# ShiftRegV1_3.net
KiCad netlist of a schematic drawn in EasyEDA
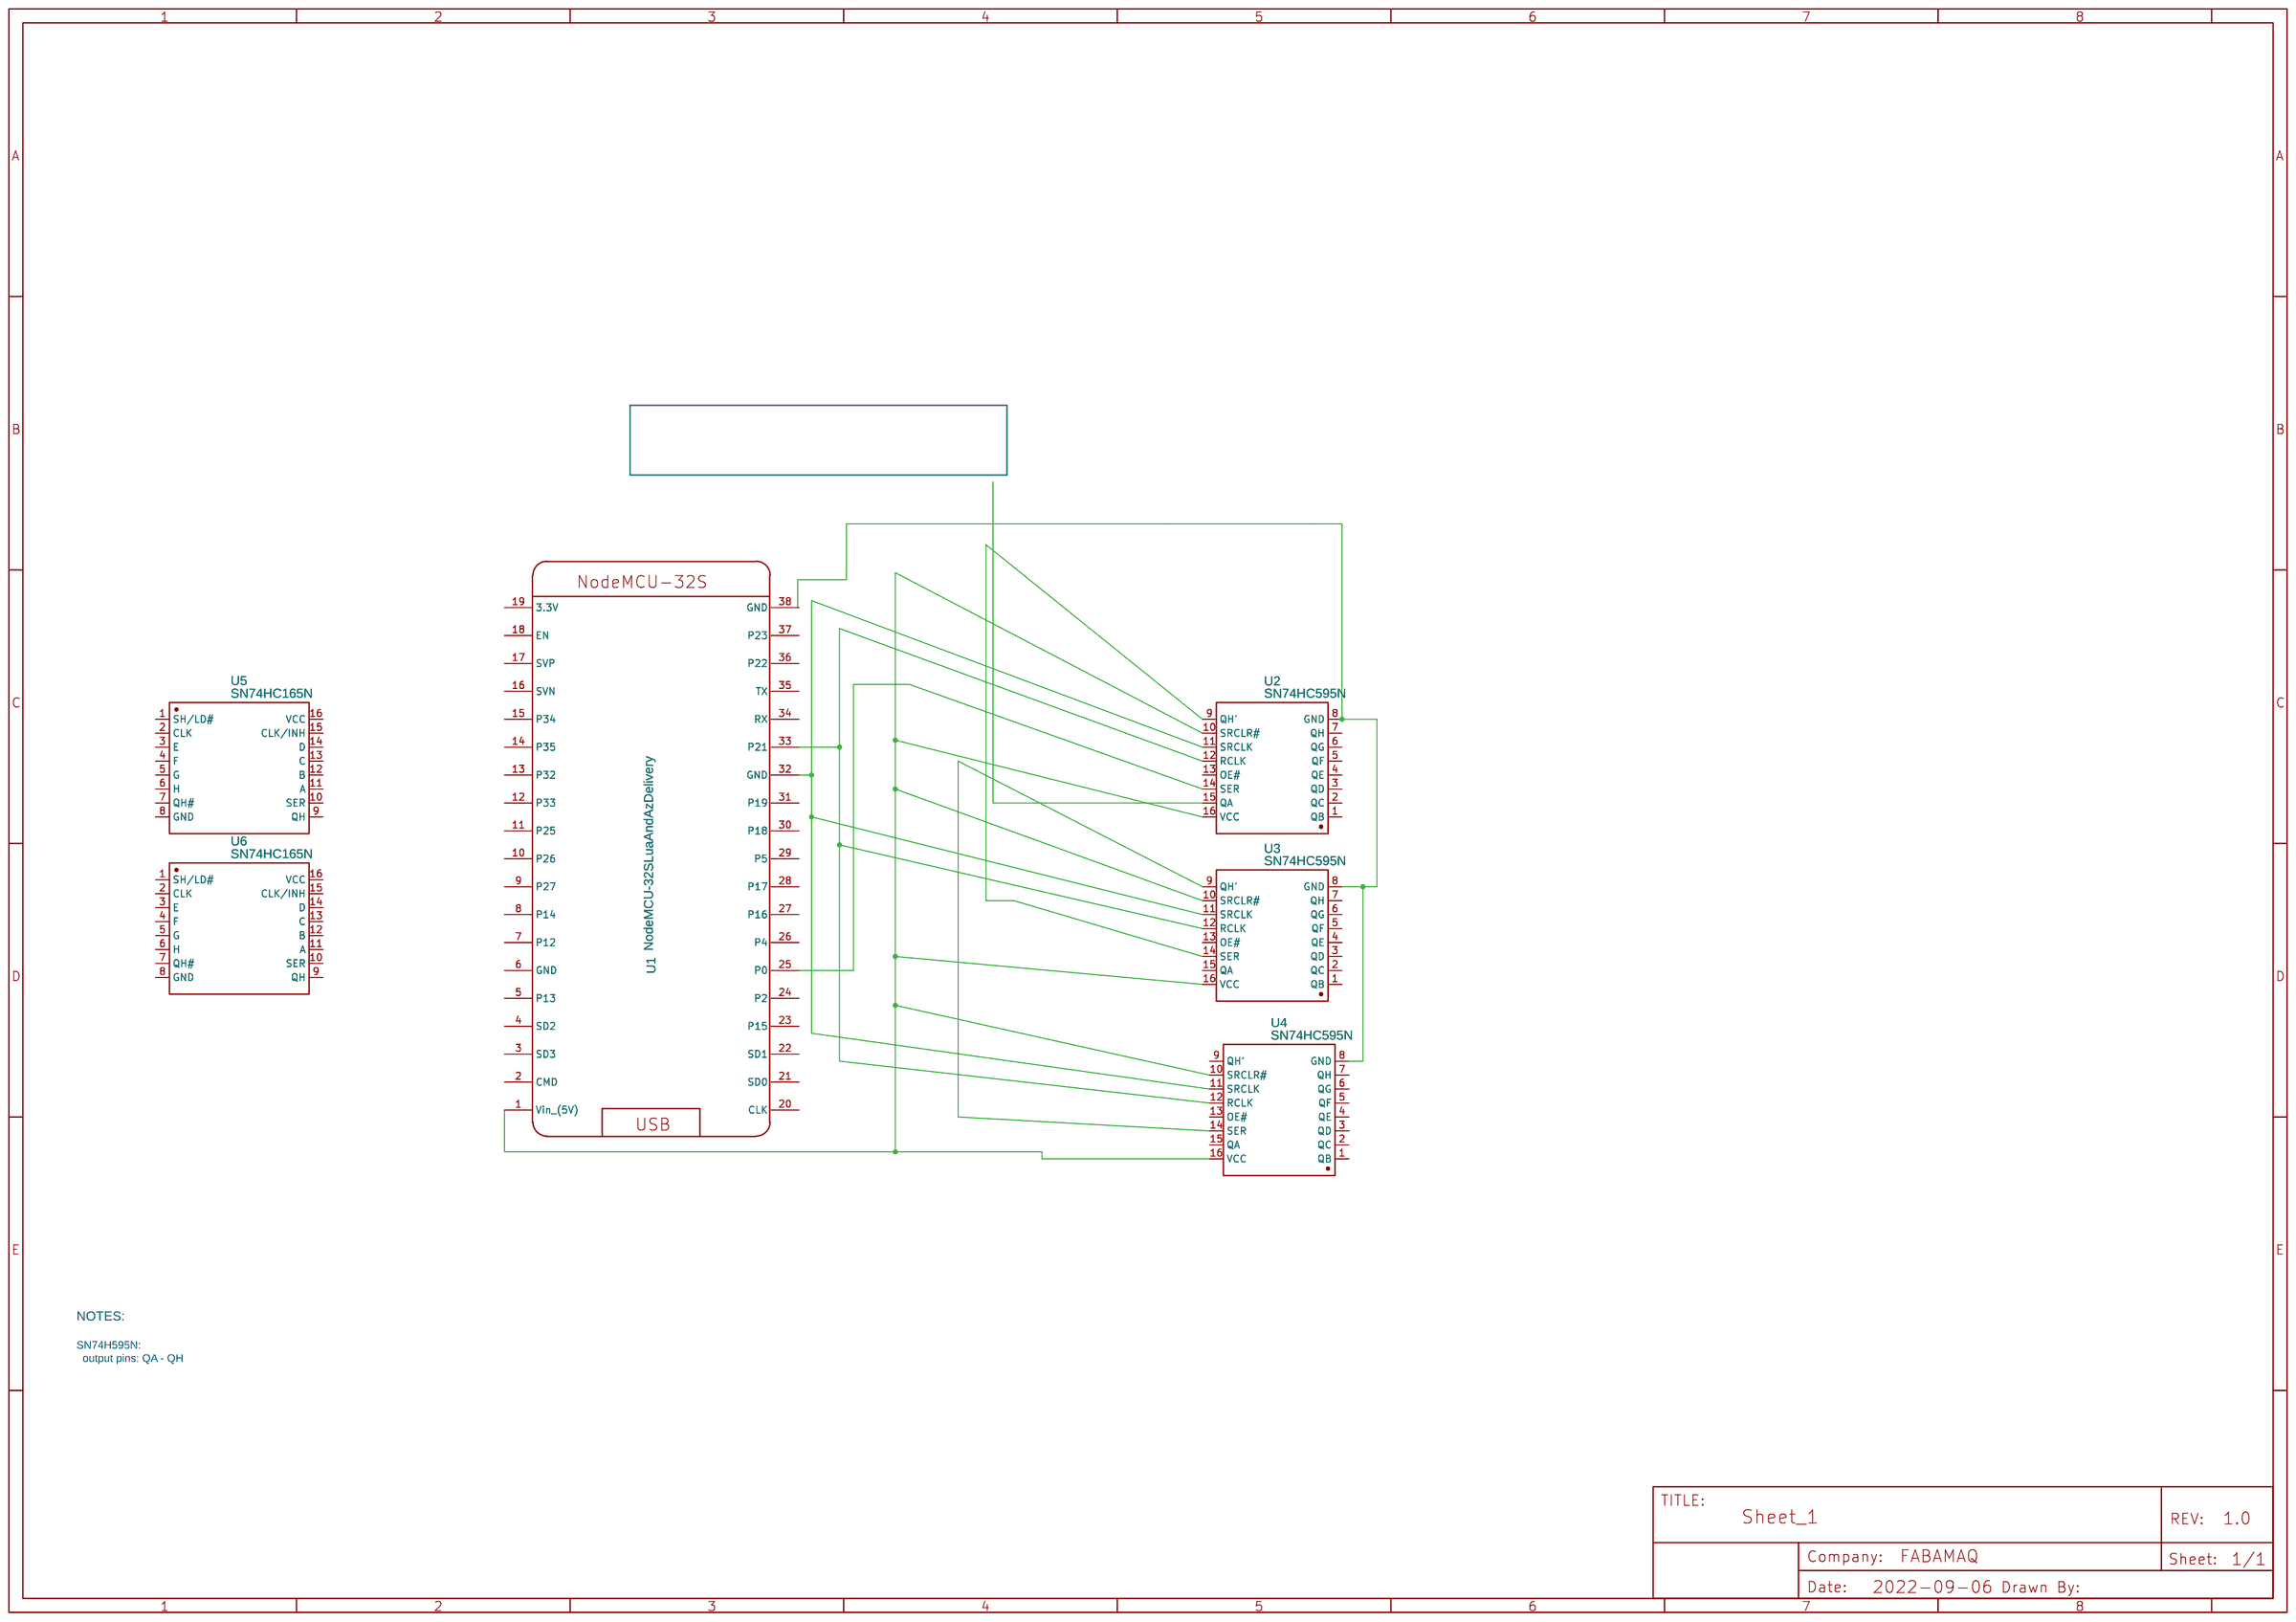
[diagram p0: schematic sheet]

(export (version "E")
  (design (tool "Eeschema 10.0.6"))
  (components
    (comp (ref "U1")
      (value "NodeMCU-32SLuaAndAzDelivery")
      (fields
        (field (name "BOM_Manufacturer Part") "NodeMCU-32SLua")
        (field (name "BOM_Supplier Part") "C111436")
      )
      (libsource (lib "") (part "NodeMCU-32SLuaAndAzDelivery"))
    )
    (comp (ref "U2")
      (value "SN74HC595N")
      (fields (field (name "BOM_Supplier Part") "C78711"))
      (libsource (lib "") (part "SN74HC595N"))
    )
    (comp (ref "U3")
      (value "SN74HC595N")
      (fields (field (name "BOM_Supplier Part") "C78711"))
      (libsource (lib "") (part "SN74HC595N"))
    )
    (comp (ref "U4")
      (value "SN74HC595N")
      (fields (field (name "BOM_Supplier Part") "C78711"))
      (libsource (lib "") (part "SN74HC595N"))
    )
    (comp (ref "U5")
      (value "SN74HC165N")
      (fields (field (name "BOM_Supplier Part") "C2909"))
      (libsource (lib "") (part "SN74HC165N"))
    )
    (comp (ref "U6")
      (value "SN74HC165N")
      (fields (field (name "BOM_Supplier Part") "C2909"))
      (libsource (lib "") (part "SN74HC165N"))
    )
  )
  (nets
    (net (code "1") (name "Net-(U1-P0)") (class "Default")
      (node (ref "U1") (pin "25") (pinfunction "P0_25") (pintype "unspecified"))
      (node (ref "U2") (pin "14") (pinfunction "SER_14") (pintype "unspecified"))
    )
    (net (code "2") (name "Net-(U1-P21)") (class "Default")
      (node (ref "U1") (pin "33") (pinfunction "P21_33") (pintype "unspecified"))
      (node (ref "U2") (pin "12") (pinfunction "RCLK_12") (pintype "unspecified"))
      (node (ref "U3") (pin "12") (pinfunction "RCLK_12") (pintype "unspecified"))
      (node (ref "U4") (pin "12") (pinfunction "RCLK_12") (pintype "unspecified"))
    )
    (net (code "3") (name "Net-(U1-Vin_(5V))") (class "Default")
      (node (ref "U1") (pin "1") (pinfunction "Vin_(5V)_1") (pintype "unspecified"))
      (node (ref "U2") (pin "10") (pinfunction "SRCLR#_10") (pintype "unspecified"))
      (node (ref "U2") (pin "16") (pinfunction "VCC_16") (pintype "unspecified"))
      (node (ref "U3") (pin "10") (pinfunction "SRCLR#_10") (pintype "unspecified"))
      (node (ref "U3") (pin "16") (pinfunction "VCC_16") (pintype "unspecified"))
      (node (ref "U4") (pin "10") (pinfunction "SRCLR#_10") (pintype "unspecified"))
      (node (ref "U4") (pin "16") (pinfunction "VCC_16") (pintype "unspecified"))
    )
    (net (code "4") (name "Net-(U2-GND)") (class "Default")
      (node (ref "U1") (pin "38") (pinfunction "GND_38") (pintype "unspecified"))
      (node (ref "U2") (pin "8") (pinfunction "GND_8") (pintype "unspecified"))
      (node (ref "U3") (pin "8") (pinfunction "GND_8") (pintype "unspecified"))
      (node (ref "U4") (pin "8") (pinfunction "GND_8") (pintype "unspecified"))
    )
    (net (code "5") (name "Net-(U2-QH')") (class "Default")
      (node (ref "U2") (pin "9") (pinfunction "QH'_9") (pintype "unspecified"))
      (node (ref "U3") (pin "14") (pinfunction "SER_14") (pintype "unspecified"))
    )
    (net (code "6") (name "Net-(U2-SRCLK)") (class "Default")
      (node (ref "U1") (pin "32") (pinfunction "GND_32") (pintype "unspecified"))
      (node (ref "U2") (pin "11") (pinfunction "SRCLK_11") (pintype "unspecified"))
      (node (ref "U3") (pin "11") (pinfunction "SRCLK_11") (pintype "unspecified"))
      (node (ref "U4") (pin "11") (pinfunction "SRCLK_11") (pintype "unspecified"))
    )
    (net (code "7") (name "Net-(U3-QH')") (class "Default")
      (node (ref "U3") (pin "9") (pinfunction "QH'_9") (pintype "unspecified"))
      (node (ref "U4") (pin "14") (pinfunction "SER_14") (pintype "unspecified"))
    )
    (net (code "8") (name "unconnected-(U1-3.3V-Pad19)") (class "Default")
      (node (ref "U1") (pin "19") (pinfunction "3.3V_19") (pintype "unspecified"))
    )
    (net (code "9") (name "unconnected-(U1-CLK-Pad20)") (class "Default")
      (node (ref "U1") (pin "20") (pinfunction "CLK_20") (pintype "unspecified"))
    )
    (net (code "10") (name "unconnected-(U1-CMD-Pad2)") (class "Default")
      (node (ref "U1") (pin "2") (pinfunction "CMD_2") (pintype "unspecified"))
    )
    (net (code "11") (name "unconnected-(U1-EN-Pad18)") (class "Default")
      (node (ref "U1") (pin "18") (pinfunction "EN_18") (pintype "unspecified"))
    )
    (net (code "12") (name "unconnected-(U1-GND-Pad6)") (class "Default")
      (node (ref "U1") (pin "6") (pinfunction "GND_6") (pintype "unspecified"))
    )
    (net (code "13") (name "unconnected-(U1-P2-Pad24)") (class "Default")
      (node (ref "U1") (pin "24") (pinfunction "P2_24") (pintype "unspecified"))
    )
    (net (code "14") (name "unconnected-(U1-P4-Pad26)") (class "Default")
      (node (ref "U1") (pin "26") (pinfunction "P4_26") (pintype "unspecified"))
    )
    (net (code "15") (name "unconnected-(U1-P5-Pad29)") (class "Default")
      (node (ref "U1") (pin "29") (pinfunction "P5_29") (pintype "unspecified"))
    )
    (net (code "16") (name "unconnected-(U1-P12-Pad7)") (class "Default")
      (node (ref "U1") (pin "7") (pinfunction "P12_7") (pintype "unspecified"))
    )
    (net (code "17") (name "unconnected-(U1-P13-Pad5)") (class "Default")
      (node (ref "U1") (pin "5") (pinfunction "P13_5") (pintype "unspecified"))
    )
    (net (code "18") (name "unconnected-(U1-P14-Pad8)") (class "Default")
      (node (ref "U1") (pin "8") (pinfunction "P14_8") (pintype "unspecified"))
    )
    (net (code "19") (name "unconnected-(U1-P15-Pad23)") (class "Default")
      (node (ref "U1") (pin "23") (pinfunction "P15_23") (pintype "unspecified"))
    )
    (net (code "20") (name "unconnected-(U1-P16-Pad27)") (class "Default")
      (node (ref "U1") (pin "27") (pinfunction "P16_27") (pintype "unspecified"))
    )
    (net (code "21") (name "unconnected-(U1-P17-Pad28)") (class "Default")
      (node (ref "U1") (pin "28") (pinfunction "P17_28") (pintype "unspecified"))
    )
    (net (code "22") (name "unconnected-(U1-P18-Pad30)") (class "Default")
      (node (ref "U1") (pin "30") (pinfunction "P18_30") (pintype "unspecified"))
    )
    (net (code "23") (name "unconnected-(U1-P19-Pad31)") (class "Default")
      (node (ref "U1") (pin "31") (pinfunction "P19_31") (pintype "unspecified"))
    )
    (net (code "24") (name "unconnected-(U1-P22-Pad36)") (class "Default")
      (node (ref "U1") (pin "36") (pinfunction "P22_36") (pintype "unspecified"))
    )
    (net (code "25") (name "unconnected-(U1-P23-Pad37)") (class "Default")
      (node (ref "U1") (pin "37") (pinfunction "P23_37") (pintype "unspecified"))
    )
    (net (code "26") (name "unconnected-(U1-P25-Pad11)") (class "Default")
      (node (ref "U1") (pin "11") (pinfunction "P25_11") (pintype "unspecified"))
    )
    (net (code "27") (name "unconnected-(U1-P26-Pad10)") (class "Default")
      (node (ref "U1") (pin "10") (pinfunction "P26_10") (pintype "unspecified"))
    )
    (net (code "28") (name "unconnected-(U1-P27-Pad9)") (class "Default")
      (node (ref "U1") (pin "9") (pinfunction "P27_9") (pintype "unspecified"))
    )
    (net (code "29") (name "unconnected-(U1-P32-Pad13)") (class "Default")
      (node (ref "U1") (pin "13") (pinfunction "P32_13") (pintype "unspecified"))
    )
    (net (code "30") (name "unconnected-(U1-P33-Pad12)") (class "Default")
      (node (ref "U1") (pin "12") (pinfunction "P33_12") (pintype "unspecified"))
    )
    (net (code "31") (name "unconnected-(U1-P34-Pad15)") (class "Default")
      (node (ref "U1") (pin "15") (pinfunction "P34_15") (pintype "unspecified"))
    )
    (net (code "32") (name "unconnected-(U1-P35-Pad14)") (class "Default")
      (node (ref "U1") (pin "14") (pinfunction "P35_14") (pintype "unspecified"))
    )
    (net (code "33") (name "unconnected-(U1-RX-Pad34)") (class "Default")
      (node (ref "U1") (pin "34") (pinfunction "RX_34") (pintype "unspecified"))
    )
    (net (code "34") (name "unconnected-(U1-SD0-Pad21)") (class "Default")
      (node (ref "U1") (pin "21") (pinfunction "SD0_21") (pintype "unspecified"))
    )
    (net (code "35") (name "unconnected-(U1-SD1-Pad22)") (class "Default")
      (node (ref "U1") (pin "22") (pinfunction "SD1_22") (pintype "unspecified"))
    )
    (net (code "36") (name "unconnected-(U1-SD2-Pad4)") (class "Default")
      (node (ref "U1") (pin "4") (pinfunction "SD2_4") (pintype "unspecified"))
    )
    (net (code "37") (name "unconnected-(U1-SD3-Pad3)") (class "Default")
      (node (ref "U1") (pin "3") (pinfunction "SD3_3") (pintype "unspecified"))
    )
    (net (code "38") (name "unconnected-(U1-SVN-Pad16)") (class "Default")
      (node (ref "U1") (pin "16") (pinfunction "SVN_16") (pintype "unspecified"))
    )
    (net (code "39") (name "unconnected-(U1-SVP-Pad17)") (class "Default")
      (node (ref "U1") (pin "17") (pinfunction "SVP_17") (pintype "unspecified"))
    )
    (net (code "40") (name "unconnected-(U1-TX-Pad35)") (class "Default")
      (node (ref "U1") (pin "35") (pinfunction "TX_35") (pintype "unspecified"))
    )
    (net (code "41") (name "unconnected-(U2-OE#-Pad13)") (class "Default")
      (node (ref "U2") (pin "13") (pinfunction "OE#_13") (pintype "unspecified"))
    )
    (net (code "42") (name "unconnected-(U2-QA-Pad15)") (class "Default")
      (node (ref "U2") (pin "15") (pinfunction "QA_15") (pintype "unspecified"))
    )
    (net (code "43") (name "unconnected-(U2-QB-Pad1)") (class "Default")
      (node (ref "U2") (pin "1") (pinfunction "QB_1") (pintype "unspecified"))
    )
    (net (code "44") (name "unconnected-(U2-QC-Pad2)") (class "Default")
      (node (ref "U2") (pin "2") (pinfunction "QC_2") (pintype "unspecified"))
    )
    (net (code "45") (name "unconnected-(U2-QD-Pad3)") (class "Default")
      (node (ref "U2") (pin "3") (pinfunction "QD_3") (pintype "unspecified"))
    )
    (net (code "46") (name "unconnected-(U2-QE-Pad4)") (class "Default")
      (node (ref "U2") (pin "4") (pinfunction "QE_4") (pintype "unspecified"))
    )
    (net (code "47") (name "unconnected-(U2-QF-Pad5)") (class "Default")
      (node (ref "U2") (pin "5") (pinfunction "QF_5") (pintype "unspecified"))
    )
    (net (code "48") (name "unconnected-(U2-QG-Pad6)") (class "Default")
      (node (ref "U2") (pin "6") (pinfunction "QG_6") (pintype "unspecified"))
    )
    (net (code "49") (name "unconnected-(U2-QH-Pad7)") (class "Default")
      (node (ref "U2") (pin "7") (pinfunction "QH_7") (pintype "unspecified"))
    )
    (net (code "50") (name "unconnected-(U3-OE#-Pad13)") (class "Default")
      (node (ref "U3") (pin "13") (pinfunction "OE#_13") (pintype "unspecified"))
    )
    (net (code "51") (name "unconnected-(U3-QA-Pad15)") (class "Default")
      (node (ref "U3") (pin "15") (pinfunction "QA_15") (pintype "unspecified"))
    )
    (net (code "52") (name "unconnected-(U3-QB-Pad1)") (class "Default")
      (node (ref "U3") (pin "1") (pinfunction "QB_1") (pintype "unspecified"))
    )
    (net (code "53") (name "unconnected-(U3-QC-Pad2)") (class "Default")
      (node (ref "U3") (pin "2") (pinfunction "QC_2") (pintype "unspecified"))
    )
    (net (code "54") (name "unconnected-(U3-QD-Pad3)") (class "Default")
      (node (ref "U3") (pin "3") (pinfunction "QD_3") (pintype "unspecified"))
    )
    (net (code "55") (name "unconnected-(U3-QE-Pad4)") (class "Default")
      (node (ref "U3") (pin "4") (pinfunction "QE_4") (pintype "unspecified"))
    )
    (net (code "56") (name "unconnected-(U3-QF-Pad5)") (class "Default")
      (node (ref "U3") (pin "5") (pinfunction "QF_5") (pintype "unspecified"))
    )
    (net (code "57") (name "unconnected-(U3-QG-Pad6)") (class "Default")
      (node (ref "U3") (pin "6") (pinfunction "QG_6") (pintype "unspecified"))
    )
    (net (code "58") (name "unconnected-(U3-QH-Pad7)") (class "Default")
      (node (ref "U3") (pin "7") (pinfunction "QH_7") (pintype "unspecified"))
    )
    (net (code "59") (name "unconnected-(U4-OE#-Pad13)") (class "Default")
      (node (ref "U4") (pin "13") (pinfunction "OE#_13") (pintype "unspecified"))
    )
    (net (code "60") (name "unconnected-(U4-QA-Pad15)") (class "Default")
      (node (ref "U4") (pin "15") (pinfunction "QA_15") (pintype "unspecified"))
    )
    (net (code "61") (name "unconnected-(U4-QB-Pad1)") (class "Default")
      (node (ref "U4") (pin "1") (pinfunction "QB_1") (pintype "unspecified"))
    )
    (net (code "62") (name "unconnected-(U4-QC-Pad2)") (class "Default")
      (node (ref "U4") (pin "2") (pinfunction "QC_2") (pintype "unspecified"))
    )
    (net (code "63") (name "unconnected-(U4-QD-Pad3)") (class "Default")
      (node (ref "U4") (pin "3") (pinfunction "QD_3") (pintype "unspecified"))
    )
    (net (code "64") (name "unconnected-(U4-QE-Pad4)") (class "Default")
      (node (ref "U4") (pin "4") (pinfunction "QE_4") (pintype "unspecified"))
    )
    (net (code "65") (name "unconnected-(U4-QF-Pad5)") (class "Default")
      (node (ref "U4") (pin "5") (pinfunction "QF_5") (pintype "unspecified"))
    )
    (net (code "66") (name "unconnected-(U4-QG-Pad6)") (class "Default")
      (node (ref "U4") (pin "6") (pinfunction "QG_6") (pintype "unspecified"))
    )
    (net (code "67") (name "unconnected-(U4-QH'-Pad9)") (class "Default")
      (node (ref "U4") (pin "9") (pinfunction "QH'_9") (pintype "unspecified"))
    )
    (net (code "68") (name "unconnected-(U4-QH-Pad7)") (class "Default")
      (node (ref "U4") (pin "7") (pinfunction "QH_7") (pintype "unspecified"))
    )
    (net (code "69") (name "unconnected-(U5-A-Pad11)") (class "Default")
      (node (ref "U5") (pin "11") (pinfunction "A_11") (pintype "unspecified"))
    )
    (net (code "70") (name "unconnected-(U5-B-Pad12)") (class "Default")
      (node (ref "U5") (pin "12") (pinfunction "B_12") (pintype "unspecified"))
    )
    (net (code "71") (name "unconnected-(U5-C-Pad13)") (class "Default")
      (node (ref "U5") (pin "13") (pinfunction "C_13") (pintype "unspecified"))
    )
    (net (code "72") (name "unconnected-(U5-CLK-Pad2)") (class "Default")
      (node (ref "U5") (pin "2") (pinfunction "CLK_2") (pintype "unspecified"))
    )
    (net (code "73") (name "unconnected-(U5-CLK{slash}INH-Pad15)") (class "Default")
      (node (ref "U5") (pin "15") (pinfunction "CLK/INH_15") (pintype "unspecified"))
    )
    (net (code "74") (name "unconnected-(U5-D-Pad14)") (class "Default")
      (node (ref "U5") (pin "14") (pinfunction "D_14") (pintype "unspecified"))
    )
    (net (code "75") (name "unconnected-(U5-E-Pad3)") (class "Default")
      (node (ref "U5") (pin "3") (pinfunction "E_3") (pintype "unspecified"))
    )
    (net (code "76") (name "unconnected-(U5-F-Pad4)") (class "Default")
      (node (ref "U5") (pin "4") (pinfunction "F_4") (pintype "unspecified"))
    )
    (net (code "77") (name "unconnected-(U5-G-Pad5)") (class "Default")
      (node (ref "U5") (pin "5") (pinfunction "G_5") (pintype "unspecified"))
    )
    (net (code "78") (name "unconnected-(U5-GND-Pad8)") (class "Default")
      (node (ref "U5") (pin "8") (pinfunction "GND_8") (pintype "unspecified"))
    )
    (net (code "79") (name "unconnected-(U5-H-Pad6)") (class "Default")
      (node (ref "U5") (pin "6") (pinfunction "H_6") (pintype "unspecified"))
    )
    (net (code "80") (name "unconnected-(U5-QH#-Pad7)") (class "Default")
      (node (ref "U5") (pin "7") (pinfunction "QH#_7") (pintype "unspecified"))
    )
    (net (code "81") (name "unconnected-(U5-QH-Pad9)") (class "Default")
      (node (ref "U5") (pin "9") (pinfunction "QH_9") (pintype "unspecified"))
    )
    (net (code "82") (name "unconnected-(U5-SER-Pad10)") (class "Default")
      (node (ref "U5") (pin "10") (pinfunction "SER_10") (pintype "unspecified"))
    )
    (net (code "83") (name "unconnected-(U5-SH{slash}LD#-Pad1)") (class "Default")
      (node (ref "U5") (pin "1") (pinfunction "SH/LD#_1") (pintype "unspecified"))
    )
    (net (code "84") (name "unconnected-(U5-VCC-Pad16)") (class "Default")
      (node (ref "U5") (pin "16") (pinfunction "VCC_16") (pintype "unspecified"))
    )
    (net (code "85") (name "unconnected-(U6-A-Pad11)") (class "Default")
      (node (ref "U6") (pin "11") (pinfunction "A_11") (pintype "unspecified"))
    )
    (net (code "86") (name "unconnected-(U6-B-Pad12)") (class "Default")
      (node (ref "U6") (pin "12") (pinfunction "B_12") (pintype "unspecified"))
    )
    (net (code "87") (name "unconnected-(U6-C-Pad13)") (class "Default")
      (node (ref "U6") (pin "13") (pinfunction "C_13") (pintype "unspecified"))
    )
    (net (code "88") (name "unconnected-(U6-CLK-Pad2)") (class "Default")
      (node (ref "U6") (pin "2") (pinfunction "CLK_2") (pintype "unspecified"))
    )
    (net (code "89") (name "unconnected-(U6-CLK{slash}INH-Pad15)") (class "Default")
      (node (ref "U6") (pin "15") (pinfunction "CLK/INH_15") (pintype "unspecified"))
    )
    (net (code "90") (name "unconnected-(U6-D-Pad14)") (class "Default")
      (node (ref "U6") (pin "14") (pinfunction "D_14") (pintype "unspecified"))
    )
    (net (code "91") (name "unconnected-(U6-E-Pad3)") (class "Default")
      (node (ref "U6") (pin "3") (pinfunction "E_3") (pintype "unspecified"))
    )
    (net (code "92") (name "unconnected-(U6-F-Pad4)") (class "Default")
      (node (ref "U6") (pin "4") (pinfunction "F_4") (pintype "unspecified"))
    )
    (net (code "93") (name "unconnected-(U6-G-Pad5)") (class "Default")
      (node (ref "U6") (pin "5") (pinfunction "G_5") (pintype "unspecified"))
    )
    (net (code "94") (name "unconnected-(U6-GND-Pad8)") (class "Default")
      (node (ref "U6") (pin "8") (pinfunction "GND_8") (pintype "unspecified"))
    )
    (net (code "95") (name "unconnected-(U6-H-Pad6)") (class "Default")
      (node (ref "U6") (pin "6") (pinfunction "H_6") (pintype "unspecified"))
    )
    (net (code "96") (name "unconnected-(U6-QH#-Pad7)") (class "Default")
      (node (ref "U6") (pin "7") (pinfunction "QH#_7") (pintype "unspecified"))
    )
    (net (code "97") (name "unconnected-(U6-QH-Pad9)") (class "Default")
      (node (ref "U6") (pin "9") (pinfunction "QH_9") (pintype "unspecified"))
    )
    (net (code "98") (name "unconnected-(U6-SER-Pad10)") (class "Default")
      (node (ref "U6") (pin "10") (pinfunction "SER_10") (pintype "unspecified"))
    )
    (net (code "99") (name "unconnected-(U6-SH{slash}LD#-Pad1)") (class "Default")
      (node (ref "U6") (pin "1") (pinfunction "SH/LD#_1") (pintype "unspecified"))
    )
    (net (code "100") (name "unconnected-(U6-VCC-Pad16)") (class "Default")
      (node (ref "U6") (pin "16") (pinfunction "VCC_16") (pintype "unspecified"))
    )
  )
)
